# nw2s-b2dsp-panel.net
KiCad netlist of a schematic drawn in EAGLE
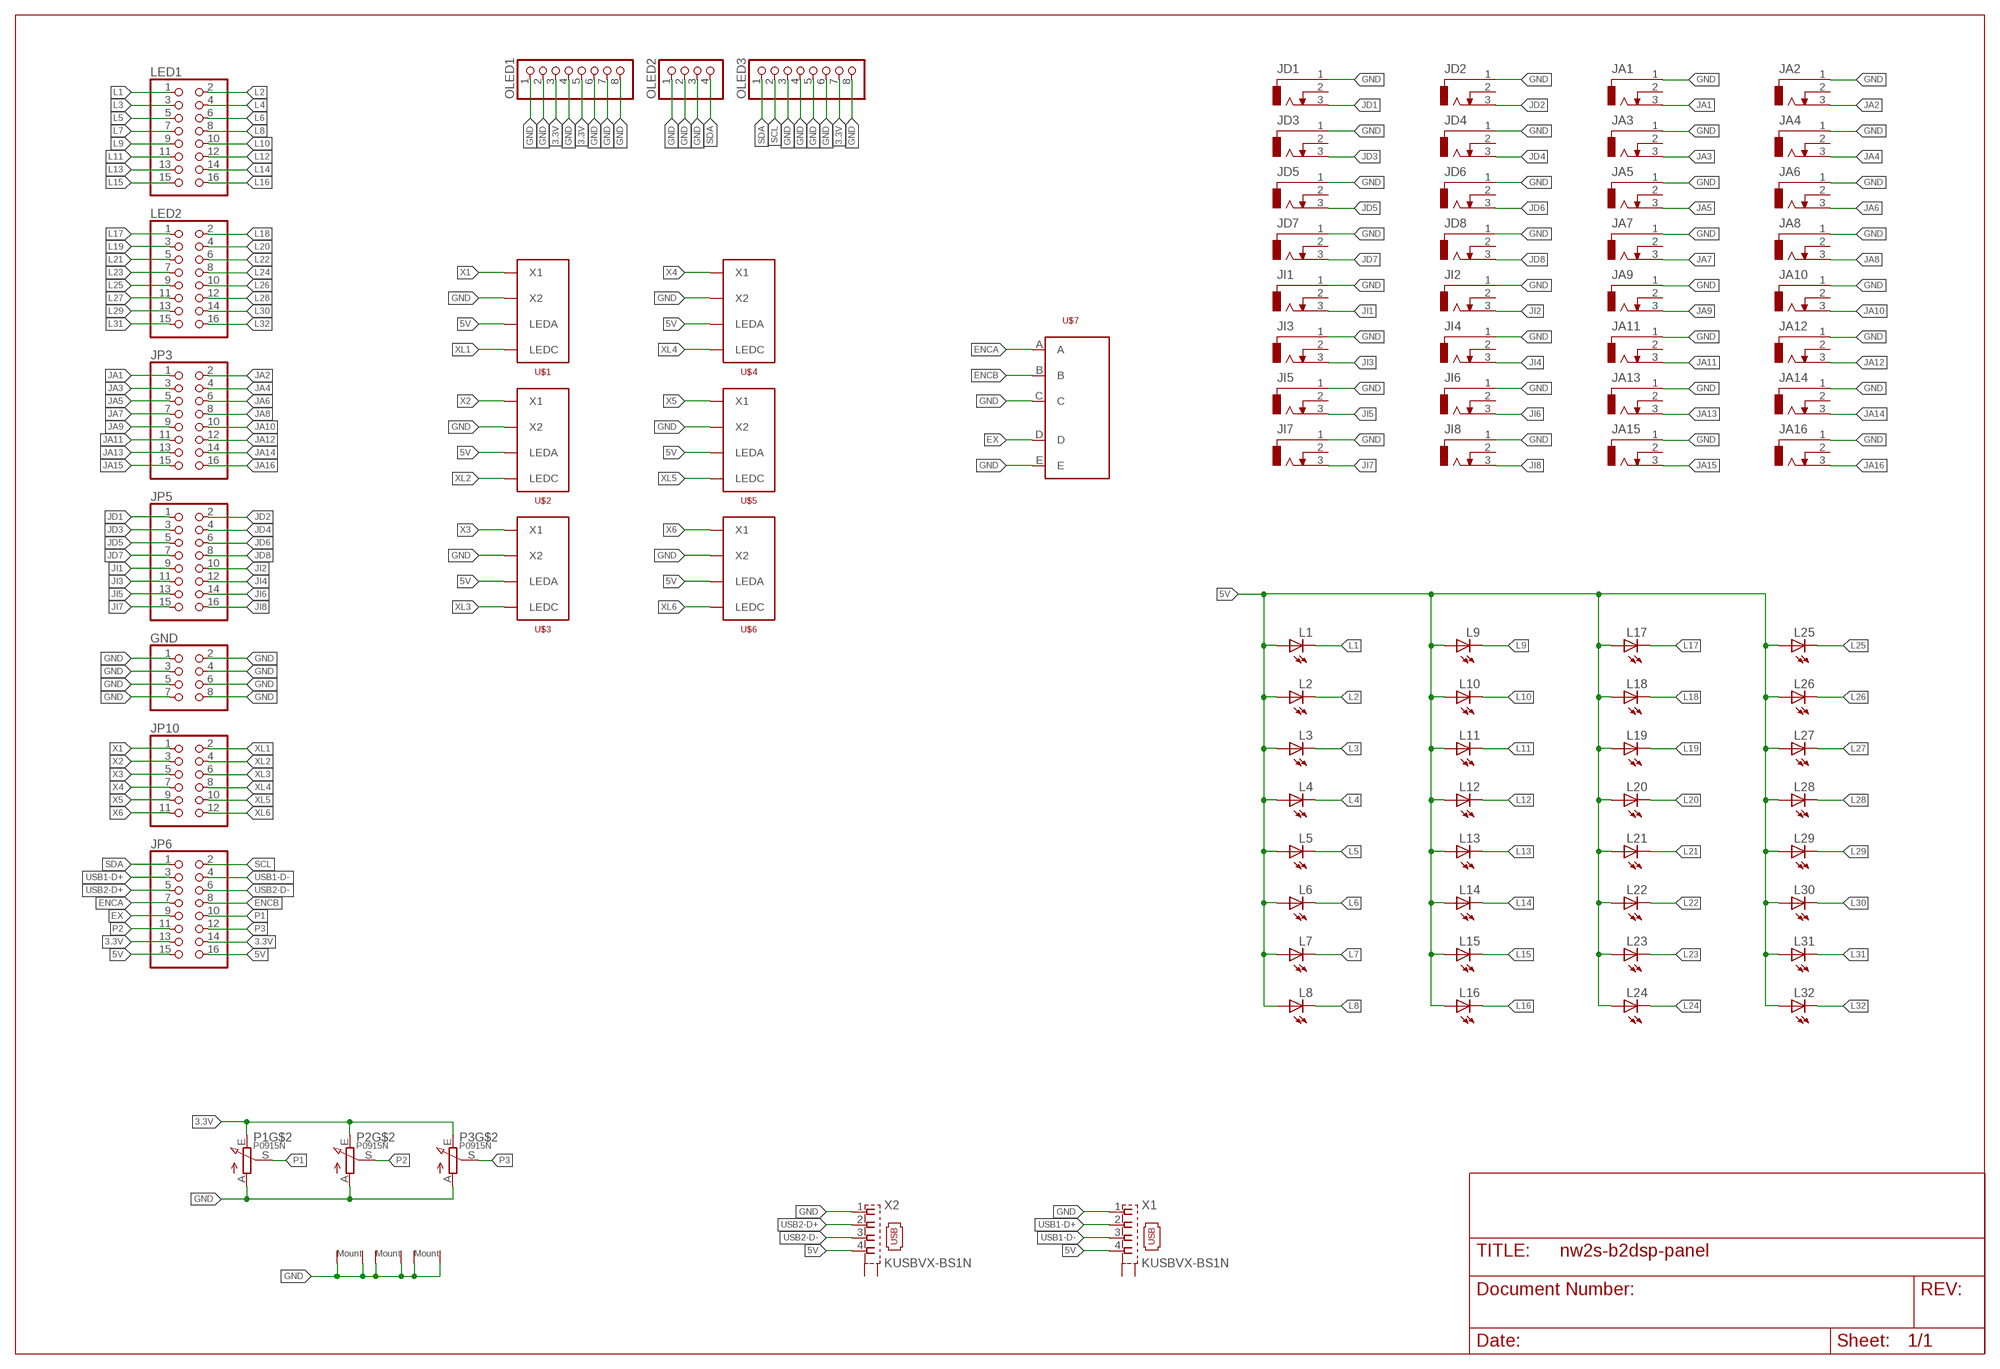
[diagram p0: schematic, sheet 1]

(export (version "E")
  (design (tool "Eeschema 10.0.6"))
  (components
    (comp (ref "GND")
      (value "PINHD-2X4")
      (footprint "eagle-import:2X04")
      (libsource (lib "eagle-import") (part "PINHD-2X4"))
    )
    (comp (ref "JA1")
      (value "THONK35A2")
      (footprint "eagle-import:THONK35A-2")
      (libsource (lib "eagle-import") (part "THONK35A2"))
    )
    (comp (ref "JA2")
      (value "THONK35A2")
      (footprint "eagle-import:THONK35A-2")
      (libsource (lib "eagle-import") (part "THONK35A2"))
    )
    (comp (ref "JA3")
      (value "THONK35A2")
      (footprint "eagle-import:THONK35A-2")
      (libsource (lib "eagle-import") (part "THONK35A2"))
    )
    (comp (ref "JA4")
      (value "THONK35A2")
      (footprint "eagle-import:THONK35A-2")
      (libsource (lib "eagle-import") (part "THONK35A2"))
    )
    (comp (ref "JA5")
      (value "THONK35A2")
      (footprint "eagle-import:THONK35A-2")
      (libsource (lib "eagle-import") (part "THONK35A2"))
    )
    (comp (ref "JA6")
      (value "THONK35A2")
      (footprint "eagle-import:THONK35A-2")
      (libsource (lib "eagle-import") (part "THONK35A2"))
    )
    (comp (ref "JA7")
      (value "THONK35A2")
      (footprint "eagle-import:THONK35A-2")
      (libsource (lib "eagle-import") (part "THONK35A2"))
    )
    (comp (ref "JA8")
      (value "THONK35A2")
      (footprint "eagle-import:THONK35A-2")
      (libsource (lib "eagle-import") (part "THONK35A2"))
    )
    (comp (ref "JA9")
      (value "THONK35A2")
      (footprint "eagle-import:THONK35A-2")
      (libsource (lib "eagle-import") (part "THONK35A2"))
    )
    (comp (ref "JA10")
      (value "THONK35A2")
      (footprint "eagle-import:THONK35A-2")
      (libsource (lib "eagle-import") (part "THONK35A2"))
    )
    (comp (ref "JA11")
      (value "THONK35A2")
      (footprint "eagle-import:THONK35A-2")
      (libsource (lib "eagle-import") (part "THONK35A2"))
    )
    (comp (ref "JA12")
      (value "THONK35A2")
      (footprint "eagle-import:THONK35A-2")
      (libsource (lib "eagle-import") (part "THONK35A2"))
    )
    (comp (ref "JA13")
      (value "THONK35A2")
      (footprint "eagle-import:THONK35A-2")
      (libsource (lib "eagle-import") (part "THONK35A2"))
    )
    (comp (ref "JA14")
      (value "THONK35A2")
      (footprint "eagle-import:THONK35A-2")
      (libsource (lib "eagle-import") (part "THONK35A2"))
    )
    (comp (ref "JA15")
      (value "THONK35A2")
      (footprint "eagle-import:THONK35A-2")
      (libsource (lib "eagle-import") (part "THONK35A2"))
    )
    (comp (ref "JA16")
      (value "THONK35A2")
      (footprint "eagle-import:THONK35A-2")
      (libsource (lib "eagle-import") (part "THONK35A2"))
    )
    (comp (ref "JD1")
      (value "THONK35A2")
      (footprint "eagle-import:THONK35A-2")
      (libsource (lib "eagle-import") (part "THONK35A2"))
    )
    (comp (ref "JD2")
      (value "THONK35A2")
      (footprint "eagle-import:THONK35A-2")
      (libsource (lib "eagle-import") (part "THONK35A2"))
    )
    (comp (ref "JD3")
      (value "THONK35A2")
      (footprint "eagle-import:THONK35A-2")
      (libsource (lib "eagle-import") (part "THONK35A2"))
    )
    (comp (ref "JD4")
      (value "THONK35A2")
      (footprint "eagle-import:THONK35A-2")
      (libsource (lib "eagle-import") (part "THONK35A2"))
    )
    (comp (ref "JD5")
      (value "THONK35A2")
      (footprint "eagle-import:THONK35A-2")
      (libsource (lib "eagle-import") (part "THONK35A2"))
    )
    (comp (ref "JD6")
      (value "THONK35A2")
      (footprint "eagle-import:THONK35A-2")
      (libsource (lib "eagle-import") (part "THONK35A2"))
    )
    (comp (ref "JD7")
      (value "THONK35A2")
      (footprint "eagle-import:THONK35A-2")
      (libsource (lib "eagle-import") (part "THONK35A2"))
    )
    (comp (ref "JD8")
      (value "THONK35A2")
      (footprint "eagle-import:THONK35A-2")
      (libsource (lib "eagle-import") (part "THONK35A2"))
    )
    (comp (ref "JI1")
      (value "THONK35A2")
      (footprint "eagle-import:THONK35A-2")
      (libsource (lib "eagle-import") (part "THONK35A2"))
    )
    (comp (ref "JI2")
      (value "THONK35A2")
      (footprint "eagle-import:THONK35A-2")
      (libsource (lib "eagle-import") (part "THONK35A2"))
    )
    (comp (ref "JI3")
      (value "THONK35A2")
      (footprint "eagle-import:THONK35A-2")
      (libsource (lib "eagle-import") (part "THONK35A2"))
    )
    (comp (ref "JI4")
      (value "THONK35A2")
      (footprint "eagle-import:THONK35A-2")
      (libsource (lib "eagle-import") (part "THONK35A2"))
    )
    (comp (ref "JI5")
      (value "THONK35A2")
      (footprint "eagle-import:THONK35A-2")
      (libsource (lib "eagle-import") (part "THONK35A2"))
    )
    (comp (ref "JI6")
      (value "THONK35A2")
      (footprint "eagle-import:THONK35A-2")
      (libsource (lib "eagle-import") (part "THONK35A2"))
    )
    (comp (ref "JI7")
      (value "THONK35A2")
      (footprint "eagle-import:THONK35A-2")
      (libsource (lib "eagle-import") (part "THONK35A2"))
    )
    (comp (ref "JI8")
      (value "THONK35A2")
      (footprint "eagle-import:THONK35A-2")
      (libsource (lib "eagle-import") (part "THONK35A2"))
    )
    (comp (ref "JP3")
      (value "PINHD-2X8")
      (footprint "eagle-import:2X08")
      (libsource (lib "eagle-import") (part "PINHD-2X8"))
    )
    (comp (ref "JP5")
      (value "PINHD-2X8")
      (footprint "eagle-import:2X08")
      (libsource (lib "eagle-import") (part "PINHD-2X8"))
    )
    (comp (ref "JP6")
      (value "PINHD-2X8")
      (footprint "eagle-import:2X08")
      (libsource (lib "eagle-import") (part "PINHD-2X8"))
    )
    (comp (ref "JP10")
      (value "PINHD-2X6")
      (footprint "eagle-import:2X06")
      (libsource (lib "eagle-import") (part "PINHD-2X6"))
    )
    (comp (ref "L1")
      (value "LED3MM")
      (footprint "eagle-import:LED3MM")
      (libsource (lib "eagle-import") (part "LED3MM"))
    )
    (comp (ref "L2")
      (value "LED3MM")
      (footprint "eagle-import:LED3MM")
      (libsource (lib "eagle-import") (part "LED3MM"))
    )
    (comp (ref "L3")
      (value "LED3MM")
      (footprint "eagle-import:LED3MM")
      (libsource (lib "eagle-import") (part "LED3MM"))
    )
    (comp (ref "L4")
      (value "LED3MM")
      (footprint "eagle-import:LED3MM")
      (libsource (lib "eagle-import") (part "LED3MM"))
    )
    (comp (ref "L5")
      (value "LED3MM")
      (footprint "eagle-import:LED3MM")
      (libsource (lib "eagle-import") (part "LED3MM"))
    )
    (comp (ref "L6")
      (value "LED3MM")
      (footprint "eagle-import:LED3MM")
      (libsource (lib "eagle-import") (part "LED3MM"))
    )
    (comp (ref "L7")
      (value "LED3MM")
      (footprint "eagle-import:LED3MM")
      (libsource (lib "eagle-import") (part "LED3MM"))
    )
    (comp (ref "L8")
      (value "LED3MM")
      (footprint "eagle-import:LED3MM")
      (libsource (lib "eagle-import") (part "LED3MM"))
    )
    (comp (ref "L9")
      (value "LED3MM")
      (footprint "eagle-import:LED3MM")
      (libsource (lib "eagle-import") (part "LED3MM"))
    )
    (comp (ref "L10")
      (value "LED3MM")
      (footprint "eagle-import:LED3MM")
      (libsource (lib "eagle-import") (part "LED3MM"))
    )
    (comp (ref "L11")
      (value "LED3MM")
      (footprint "eagle-import:LED3MM")
      (libsource (lib "eagle-import") (part "LED3MM"))
    )
    (comp (ref "L12")
      (value "LED3MM")
      (footprint "eagle-import:LED3MM")
      (libsource (lib "eagle-import") (part "LED3MM"))
    )
    (comp (ref "L13")
      (value "LED3MM")
      (footprint "eagle-import:LED3MM")
      (libsource (lib "eagle-import") (part "LED3MM"))
    )
    (comp (ref "L14")
      (value "LED3MM")
      (footprint "eagle-import:LED3MM")
      (libsource (lib "eagle-import") (part "LED3MM"))
    )
    (comp (ref "L15")
      (value "LED3MM")
      (footprint "eagle-import:LED3MM")
      (libsource (lib "eagle-import") (part "LED3MM"))
    )
    (comp (ref "L16")
      (value "LED3MM")
      (footprint "eagle-import:LED3MM")
      (libsource (lib "eagle-import") (part "LED3MM"))
    )
    (comp (ref "L17")
      (value "LED3MM")
      (footprint "eagle-import:LED3MM")
      (libsource (lib "eagle-import") (part "LED3MM"))
    )
    (comp (ref "L18")
      (value "LED3MM")
      (footprint "eagle-import:LED3MM")
      (libsource (lib "eagle-import") (part "LED3MM"))
    )
    (comp (ref "L19")
      (value "LED3MM")
      (footprint "eagle-import:LED3MM")
      (libsource (lib "eagle-import") (part "LED3MM"))
    )
    (comp (ref "L20")
      (value "LED3MM")
      (footprint "eagle-import:LED3MM")
      (libsource (lib "eagle-import") (part "LED3MM"))
    )
    (comp (ref "L21")
      (value "LED3MM")
      (footprint "eagle-import:LED3MM")
      (libsource (lib "eagle-import") (part "LED3MM"))
    )
    (comp (ref "L22")
      (value "LED3MM")
      (footprint "eagle-import:LED3MM")
      (libsource (lib "eagle-import") (part "LED3MM"))
    )
    (comp (ref "L23")
      (value "LED3MM")
      (footprint "eagle-import:LED3MM")
      (libsource (lib "eagle-import") (part "LED3MM"))
    )
    (comp (ref "L24")
      (value "LED3MM")
      (footprint "eagle-import:LED3MM")
      (libsource (lib "eagle-import") (part "LED3MM"))
    )
    (comp (ref "L25")
      (value "LED3MM")
      (footprint "eagle-import:LED3MM")
      (libsource (lib "eagle-import") (part "LED3MM"))
    )
    (comp (ref "L26")
      (value "LED3MM")
      (footprint "eagle-import:LED3MM")
      (libsource (lib "eagle-import") (part "LED3MM"))
    )
    (comp (ref "L27")
      (value "LED3MM")
      (footprint "eagle-import:LED3MM")
      (libsource (lib "eagle-import") (part "LED3MM"))
    )
    (comp (ref "L28")
      (value "LED3MM")
      (footprint "eagle-import:LED3MM")
      (libsource (lib "eagle-import") (part "LED3MM"))
    )
    (comp (ref "L29")
      (value "LED3MM")
      (footprint "eagle-import:LED3MM")
      (libsource (lib "eagle-import") (part "LED3MM"))
    )
    (comp (ref "L30")
      (value "LED3MM")
      (footprint "eagle-import:LED3MM")
      (libsource (lib "eagle-import") (part "LED3MM"))
    )
    (comp (ref "L31")
      (value "LED3MM")
      (footprint "eagle-import:LED3MM")
      (libsource (lib "eagle-import") (part "LED3MM"))
    )
    (comp (ref "L32")
      (value "LED3MM")
      (footprint "eagle-import:LED3MM")
      (libsource (lib "eagle-import") (part "LED3MM"))
    )
    (comp (ref "LED1")
      (value "PINHD-2X8")
      (footprint "eagle-import:2X08")
      (libsource (lib "eagle-import") (part "PINHD-2X8"))
    )
    (comp (ref "LED2")
      (value "PINHD-2X8")
      (footprint "eagle-import:2X08")
      (libsource (lib "eagle-import") (part "PINHD-2X8"))
    )
    (comp (ref "OLED1")
      (value "PINHD-1X8")
      (footprint "eagle-import:1X08")
      (libsource (lib "eagle-import") (part "PINHD-1X8"))
    )
    (comp (ref "OLED2")
      (value "PINHD-1X4")
      (footprint "eagle-import:1X04")
      (libsource (lib "eagle-import") (part "PINHD-1X4"))
    )
    (comp (ref "OLED3")
      (value "PINHD-1X8")
      (footprint "eagle-import:1X08")
      (libsource (lib "eagle-import") (part "PINHD-1X8"))
    )
    (comp (ref "P1")
      (value "P0915N")
      (footprint "eagle-import:P0915N")
      (libsource (lib "eagle-import") (part "P0915N"))
    )
    (comp (ref "P2")
      (value "P0915N")
      (footprint "eagle-import:P0915N")
      (libsource (lib "eagle-import") (part "P0915N"))
    )
    (comp (ref "P3")
      (value "P0915N")
      (footprint "eagle-import:P0915N")
      (libsource (lib "eagle-import") (part "P0915N"))
    )
    (comp (ref "U$1")
      (value "MEC5G")
      (footprint "eagle-import:MEC5G")
      (libsource (lib "eagle-import") (part "MEC5G"))
    )
    (comp (ref "U$2")
      (value "MEC5G")
      (footprint "eagle-import:MEC5G")
      (libsource (lib "eagle-import") (part "MEC5G"))
    )
    (comp (ref "U$3")
      (value "MEC5G")
      (footprint "eagle-import:MEC5G")
      (libsource (lib "eagle-import") (part "MEC5G"))
    )
    (comp (ref "U$4")
      (value "MEC5G")
      (footprint "eagle-import:MEC5G")
      (libsource (lib "eagle-import") (part "MEC5G"))
    )
    (comp (ref "U$5")
      (value "MEC5G")
      (footprint "eagle-import:MEC5G")
      (libsource (lib "eagle-import") (part "MEC5G"))
    )
    (comp (ref "U$6")
      (value "MEC5G")
      (footprint "eagle-import:MEC5G")
      (libsource (lib "eagle-import") (part "MEC5G"))
    )
    (comp (ref "U$7")
      (value "EN11X")
      (footprint "eagle-import:EN11")
      (libsource (lib "eagle-import") (part "EN11X"))
    )
    (comp (ref "X1")
      (value "KUSBVX-BS1N")
      (footprint "eagle-import:KUSBVX-BS1N")
      (libsource (lib "eagle-import") (part "KUSBVX-BS1N"))
    )
    (comp (ref "X2")
      (value "KUSBVX-BS1N")
      (footprint "eagle-import:KUSBVX-BS1N")
      (libsource (lib "eagle-import") (part "KUSBVX-BS1N"))
    )
  )
  (nets
    (net (code "1") (name "3.3V") (class "Default")
      (node (ref "JP6") (pin "13") (pinfunction "13_13") (pintype "passive"))
      (node (ref "JP6") (pin "14") (pinfunction "14_14") (pintype "passive"))
      (node (ref "OLED1") (pin "3") (pinfunction "3_3") (pintype "passive"))
      (node (ref "OLED1") (pin "5") (pinfunction "5_5") (pintype "passive"))
      (node (ref "OLED3") (pin "7") (pinfunction "7_7") (pintype "passive"))
      (node (ref "P1") (pin "E") (pinfunction "E_E") (pintype "passive"))
      (node (ref "P2") (pin "E") (pinfunction "E_E") (pintype "passive"))
      (node (ref "P3") (pin "E") (pinfunction "E_E") (pintype "passive"))
    )
    (net (code "2") (name "5V") (class "Default")
      (node (ref "JP6") (pin "15") (pinfunction "15_15") (pintype "passive"))
      (node (ref "JP6") (pin "16") (pinfunction "16_16") (pintype "passive"))
      (node (ref "L1") (pin "A") (pinfunction "A_A") (pintype "passive"))
      (node (ref "L10") (pin "A") (pinfunction "A_A") (pintype "passive"))
      (node (ref "L11") (pin "A") (pinfunction "A_A") (pintype "passive"))
      (node (ref "L12") (pin "A") (pinfunction "A_A") (pintype "passive"))
      (node (ref "L13") (pin "A") (pinfunction "A_A") (pintype "passive"))
      (node (ref "L14") (pin "A") (pinfunction "A_A") (pintype "passive"))
      (node (ref "L15") (pin "A") (pinfunction "A_A") (pintype "passive"))
      (node (ref "L16") (pin "A") (pinfunction "A_A") (pintype "passive"))
      (node (ref "L17") (pin "A") (pinfunction "A_A") (pintype "passive"))
      (node (ref "L18") (pin "A") (pinfunction "A_A") (pintype "passive"))
      (node (ref "L19") (pin "A") (pinfunction "A_A") (pintype "passive"))
      (node (ref "L2") (pin "A") (pinfunction "A_A") (pintype "passive"))
      (node (ref "L20") (pin "A") (pinfunction "A_A") (pintype "passive"))
      (node (ref "L21") (pin "A") (pinfunction "A_A") (pintype "passive"))
      (node (ref "L22") (pin "A") (pinfunction "A_A") (pintype "passive"))
      (node (ref "L23") (pin "A") (pinfunction "A_A") (pintype "passive"))
      (node (ref "L24") (pin "A") (pinfunction "A_A") (pintype "passive"))
      (node (ref "L25") (pin "A") (pinfunction "A_A") (pintype "passive"))
      (node (ref "L26") (pin "A") (pinfunction "A_A") (pintype "passive"))
      (node (ref "L27") (pin "A") (pinfunction "A_A") (pintype "passive"))
      (node (ref "L28") (pin "A") (pinfunction "A_A") (pintype "passive"))
      (node (ref "L29") (pin "A") (pinfunction "A_A") (pintype "passive"))
      (node (ref "L3") (pin "A") (pinfunction "A_A") (pintype "passive"))
      (node (ref "L30") (pin "A") (pinfunction "A_A") (pintype "passive"))
      (node (ref "L31") (pin "A") (pinfunction "A_A") (pintype "passive"))
      (node (ref "L32") (pin "A") (pinfunction "A_A") (pintype "passive"))
      (node (ref "L4") (pin "A") (pinfunction "A_A") (pintype "passive"))
      (node (ref "L5") (pin "A") (pinfunction "A_A") (pintype "passive"))
      (node (ref "L6") (pin "A") (pinfunction "A_A") (pintype "passive"))
      (node (ref "L7") (pin "A") (pinfunction "A_A") (pintype "passive"))
      (node (ref "L8") (pin "A") (pinfunction "A_A") (pintype "passive"))
      (node (ref "L9") (pin "A") (pinfunction "A_A") (pintype "passive"))
      (node (ref "U$1") (pin "P$4") (pinfunction "LEDA_P$4") (pintype "bidirectional"))
      (node (ref "U$2") (pin "P$4") (pinfunction "LEDA_P$4") (pintype "bidirectional"))
      (node (ref "U$3") (pin "P$4") (pinfunction "LEDA_P$4") (pintype "bidirectional"))
      (node (ref "U$4") (pin "P$4") (pinfunction "LEDA_P$4") (pintype "bidirectional"))
      (node (ref "U$5") (pin "P$4") (pinfunction "LEDA_P$4") (pintype "bidirectional"))
      (node (ref "U$6") (pin "P$4") (pinfunction "LEDA_P$4") (pintype "bidirectional"))
      (node (ref "X1") (pin "4") (pinfunction "4_4") (pintype "passive"))
      (node (ref "X2") (pin "4") (pinfunction "4_4") (pintype "passive"))
    )
    (net (code "3") (name "ENCA") (class "Default")
      (node (ref "JP6") (pin "7") (pinfunction "7_7") (pintype "passive"))
      (node (ref "U$7") (pin "A") (pinfunction "A_A") (pintype "bidirectional"))
    )
    (net (code "4") (name "ENCB") (class "Default")
      (node (ref "JP6") (pin "8") (pinfunction "8_8") (pintype "passive"))
      (node (ref "U$7") (pin "B") (pinfunction "B_B") (pintype "bidirectional"))
    )
    (net (code "5") (name "EX") (class "Default")
      (node (ref "JP6") (pin "9") (pinfunction "9_9") (pintype "passive"))
      (node (ref "U$7") (pin "D") (pinfunction "D_D") (pintype "bidirectional"))
    )
    (net (code "6") (name "GND") (class "Default")
      (node (ref "GND") (pin "1") (pinfunction "1_1") (pintype "passive"))
      (node (ref "GND") (pin "2") (pinfunction "2_2") (pintype "passive"))
      (node (ref "GND") (pin "3") (pinfunction "3_3") (pintype "passive"))
      (node (ref "GND") (pin "4") (pinfunction "4_4") (pintype "passive"))
      (node (ref "GND") (pin "5") (pinfunction "5_5") (pintype "passive"))
      (node (ref "GND") (pin "6") (pinfunction "6_6") (pintype "passive"))
      (node (ref "GND") (pin "7") (pinfunction "7_7") (pintype "passive"))
      (node (ref "GND") (pin "8") (pinfunction "8_8") (pintype "passive"))
      (node (ref "JA1") (pin "1") (pinfunction "1_1") (pintype "passive"))
      (node (ref "JA10") (pin "1") (pinfunction "1_1") (pintype "passive"))
      (node (ref "JA11") (pin "1") (pinfunction "1_1") (pintype "passive"))
      (node (ref "JA12") (pin "1") (pinfunction "1_1") (pintype "passive"))
      (node (ref "JA13") (pin "1") (pinfunction "1_1") (pintype "passive"))
      (node (ref "JA14") (pin "1") (pinfunction "1_1") (pintype "passive"))
      (node (ref "JA15") (pin "1") (pinfunction "1_1") (pintype "passive"))
      (node (ref "JA16") (pin "1") (pinfunction "1_1") (pintype "passive"))
      (node (ref "JA2") (pin "1") (pinfunction "1_1") (pintype "passive"))
      (node (ref "JA3") (pin "1") (pinfunction "1_1") (pintype "passive"))
      (node (ref "JA4") (pin "1") (pinfunction "1_1") (pintype "passive"))
      (node (ref "JA5") (pin "1") (pinfunction "1_1") (pintype "passive"))
      (node (ref "JA6") (pin "1") (pinfunction "1_1") (pintype "passive"))
      (node (ref "JA7") (pin "1") (pinfunction "1_1") (pintype "passive"))
      (node (ref "JA8") (pin "1") (pinfunction "1_1") (pintype "passive"))
      (node (ref "JA9") (pin "1") (pinfunction "1_1") (pintype "passive"))
      (node (ref "JD1") (pin "1") (pinfunction "1_1") (pintype "passive"))
      (node (ref "JD2") (pin "1") (pinfunction "1_1") (pintype "passive"))
      (node (ref "JD3") (pin "1") (pinfunction "1_1") (pintype "passive"))
      (node (ref "JD4") (pin "1") (pinfunction "1_1") (pintype "passive"))
      (node (ref "JD5") (pin "1") (pinfunction "1_1") (pintype "passive"))
      (node (ref "JD6") (pin "1") (pinfunction "1_1") (pintype "passive"))
      (node (ref "JD7") (pin "1") (pinfunction "1_1") (pintype "passive"))
      (node (ref "JD8") (pin "1") (pinfunction "1_1") (pintype "passive"))
      (node (ref "JI1") (pin "1") (pinfunction "1_1") (pintype "passive"))
      (node (ref "JI2") (pin "1") (pinfunction "1_1") (pintype "passive"))
      (node (ref "JI3") (pin "1") (pinfunction "1_1") (pintype "passive"))
      (node (ref "JI4") (pin "1") (pinfunction "1_1") (pintype "passive"))
      (node (ref "JI5") (pin "1") (pinfunction "1_1") (pintype "passive"))
      (node (ref "JI6") (pin "1") (pinfunction "1_1") (pintype "passive"))
      (node (ref "JI7") (pin "1") (pinfunction "1_1") (pintype "passive"))
      (node (ref "JI8") (pin "1") (pinfunction "1_1") (pintype "passive"))
      (node (ref "OLED1") (pin "1") (pinfunction "1_1") (pintype "passive"))
      (node (ref "OLED1") (pin "2") (pinfunction "2_2") (pintype "passive"))
      (node (ref "OLED1") (pin "4") (pinfunction "4_4") (pintype "passive"))
      (node (ref "OLED1") (pin "6") (pinfunction "6_6") (pintype "passive"))
      (node (ref "OLED1") (pin "7") (pinfunction "7_7") (pintype "passive"))
      (node (ref "OLED1") (pin "8") (pinfunction "8_8") (pintype "passive"))
      (node (ref "OLED2") (pin "1") (pinfunction "1_1") (pintype "passive"))
      (node (ref "OLED2") (pin "2") (pinfunction "2_2") (pintype "passive"))
      (node (ref "OLED2") (pin "3") (pinfunction "3_3") (pintype "passive"))
      (node (ref "OLED3") (pin "3") (pinfunction "3_3") (pintype "passive"))
      (node (ref "OLED3") (pin "4") (pinfunction "4_4") (pintype "passive"))
      (node (ref "OLED3") (pin "5") (pinfunction "5_5") (pintype "passive"))
      (node (ref "OLED3") (pin "6") (pinfunction "6_6") (pintype "passive"))
      (node (ref "OLED3") (pin "8") (pinfunction "8_8") (pintype "passive"))
      (node (ref "P1") (pin "A") (pinfunction "A_A") (pintype "passive"))
      (node (ref "P1") (pin "GND@1") (pinfunction "GND_GND@1") (pintype "passive"))
      (node (ref "P1") (pin "GND@2") (pinfunction "GND_GND@2") (pintype "passive"))
      (node (ref "P2") (pin "A") (pinfunction "A_A") (pintype "passive"))
      (node (ref "P2") (pin "GND@1") (pinfunction "GND_GND@1") (pintype "passive"))
      (node (ref "P2") (pin "GND@2") (pinfunction "GND_GND@2") (pintype "passive"))
      (node (ref "P3") (pin "A") (pinfunction "A_A") (pintype "passive"))
      (node (ref "P3") (pin "GND@1") (pinfunction "GND_GND@1") (pintype "passive"))
      (node (ref "P3") (pin "GND@2") (pinfunction "GND_GND@2") (pintype "passive"))
      (node (ref "U$1") (pin "P$3") (pinfunction "X2_P$3") (pintype "bidirectional"))
      (node (ref "U$2") (pin "P$3") (pinfunction "X2_P$3") (pintype "bidirectional"))
      (node (ref "U$3") (pin "P$3") (pinfunction "X2_P$3") (pintype "bidirectional"))
      (node (ref "U$4") (pin "P$3") (pinfunction "X2_P$3") (pintype "bidirectional"))
      (node (ref "U$5") (pin "P$3") (pinfunction "X2_P$3") (pintype "bidirectional"))
      (node (ref "U$6") (pin "P$3") (pinfunction "X2_P$3") (pintype "bidirectional"))
      (node (ref "U$7") (pin "C") (pinfunction "C_C") (pintype "bidirectional"))
      (node (ref "U$7") (pin "E") (pinfunction "E_E") (pintype "bidirectional"))
      (node (ref "X1") (pin "1") (pinfunction "1_1") (pintype "passive"))
      (node (ref "X2") (pin "1") (pinfunction "1_1") (pintype "passive"))
    )
    (net (code "7") (name "JA1") (class "Default")
      (node (ref "JA1") (pin "3") (pinfunction "3_3") (pintype "passive"))
      (node (ref "JP3") (pin "1") (pinfunction "1_1") (pintype "passive"))
    )
    (net (code "8") (name "JA2") (class "Default")
      (node (ref "JA2") (pin "3") (pinfunction "3_3") (pintype "passive"))
      (node (ref "JP3") (pin "2") (pinfunction "2_2") (pintype "passive"))
    )
    (net (code "9") (name "JA3") (class "Default")
      (node (ref "JA3") (pin "3") (pinfunction "3_3") (pintype "passive"))
      (node (ref "JP3") (pin "3") (pinfunction "3_3") (pintype "passive"))
    )
    (net (code "10") (name "JA4") (class "Default")
      (node (ref "JA4") (pin "3") (pinfunction "3_3") (pintype "passive"))
      (node (ref "JP3") (pin "4") (pinfunction "4_4") (pintype "passive"))
    )
    (net (code "11") (name "JA5") (class "Default")
      (node (ref "JA5") (pin "3") (pinfunction "3_3") (pintype "passive"))
      (node (ref "JP3") (pin "5") (pinfunction "5_5") (pintype "passive"))
    )
    (net (code "12") (name "JA6") (class "Default")
      (node (ref "JA6") (pin "3") (pinfunction "3_3") (pintype "passive"))
      (node (ref "JP3") (pin "6") (pinfunction "6_6") (pintype "passive"))
    )
    (net (code "13") (name "JA7") (class "Default")
      (node (ref "JA7") (pin "3") (pinfunction "3_3") (pintype "passive"))
      (node (ref "JP3") (pin "7") (pinfunction "7_7") (pintype "passive"))
    )
    (net (code "14") (name "JA8") (class "Default")
      (node (ref "JA8") (pin "3") (pinfunction "3_3") (pintype "passive"))
      (node (ref "JP3") (pin "8") (pinfunction "8_8") (pintype "passive"))
    )
    (net (code "15") (name "JA9") (class "Default")
      (node (ref "JA9") (pin "3") (pinfunction "3_3") (pintype "passive"))
      (node (ref "JP3") (pin "9") (pinfunction "9_9") (pintype "passive"))
    )
    (net (code "16") (name "JA10") (class "Default")
      (node (ref "JA10") (pin "3") (pinfunction "3_3") (pintype "passive"))
      (node (ref "JP3") (pin "10") (pinfunction "10_10") (pintype "passive"))
    )
    (net (code "17") (name "JA11") (class "Default")
      (node (ref "JA11") (pin "3") (pinfunction "3_3") (pintype "passive"))
      (node (ref "JP3") (pin "11") (pinfunction "11_11") (pintype "passive"))
    )
    (net (code "18") (name "JA12") (class "Default")
      (node (ref "JA12") (pin "3") (pinfunction "3_3") (pintype "passive"))
      (node (ref "JP3") (pin "12") (pinfunction "12_12") (pintype "passive"))
    )
    (net (code "19") (name "JA13") (class "Default")
      (node (ref "JA13") (pin "3") (pinfunction "3_3") (pintype "passive"))
      (node (ref "JP3") (pin "13") (pinfunction "13_13") (pintype "passive"))
    )
    (net (code "20") (name "JA14") (class "Default")
      (node (ref "JA14") (pin "3") (pinfunction "3_3") (pintype "passive"))
      (node (ref "JP3") (pin "14") (pinfunction "14_14") (pintype "passive"))
    )
    (net (code "21") (name "JA15") (class "Default")
      (node (ref "JA15") (pin "3") (pinfunction "3_3") (pintype "passive"))
      (node (ref "JP3") (pin "15") (pinfunction "15_15") (pintype "passive"))
    )
    (net (code "22") (name "JA16") (class "Default")
      (node (ref "JA16") (pin "3") (pinfunction "3_3") (pintype "passive"))
      (node (ref "JP3") (pin "16") (pinfunction "16_16") (pintype "passive"))
    )
    (net (code "23") (name "JD1") (class "Default")
      (node (ref "JD1") (pin "3") (pinfunction "3_3") (pintype "passive"))
      (node (ref "JP5") (pin "1") (pinfunction "1_1") (pintype "passive"))
    )
    (net (code "24") (name "JD2") (class "Default")
      (node (ref "JD2") (pin "3") (pinfunction "3_3") (pintype "passive"))
      (node (ref "JP5") (pin "2") (pinfunction "2_2") (pintype "passive"))
    )
    (net (code "25") (name "JD3") (class "Default")
      (node (ref "JD3") (pin "3") (pinfunction "3_3") (pintype "passive"))
      (node (ref "JP5") (pin "3") (pinfunction "3_3") (pintype "passive"))
    )
    (net (code "26") (name "JD4") (class "Default")
      (node (ref "JD4") (pin "3") (pinfunction "3_3") (pintype "passive"))
      (node (ref "JP5") (pin "4") (pinfunction "4_4") (pintype "passive"))
    )
    (net (code "27") (name "JD5") (class "Default")
      (node (ref "JD5") (pin "3") (pinfunction "3_3") (pintype "passive"))
      (node (ref "JP5") (pin "5") (pinfunction "5_5") (pintype "passive"))
    )
    (net (code "28") (name "JD6") (class "Default")
      (node (ref "JD6") (pin "3") (pinfunction "3_3") (pintype "passive"))
      (node (ref "JP5") (pin "6") (pinfunction "6_6") (pintype "passive"))
    )
    (net (code "29") (name "JD7") (class "Default")
      (node (ref "JD7") (pin "3") (pinfunction "3_3") (pintype "passive"))
      (node (ref "JP5") (pin "7") (pinfunction "7_7") (pintype "passive"))
    )
    (net (code "30") (name "JD8") (class "Default")
      (node (ref "JD8") (pin "3") (pinfunction "3_3") (pintype "passive"))
      (node (ref "JP5") (pin "8") (pinfunction "8_8") (pintype "passive"))
    )
    (net (code "31") (name "JI1") (class "Default")
      (node (ref "JI1") (pin "3") (pinfunction "3_3") (pintype "passive"))
      (node (ref "JP5") (pin "9") (pinfunction "9_9") (pintype "passive"))
    )
    (net (code "32") (name "JI2") (class "Default")
      (node (ref "JI2") (pin "3") (pinfunction "3_3") (pintype "passive"))
      (node (ref "JP5") (pin "10") (pinfunction "10_10") (pintype "passive"))
    )
    (net (code "33") (name "JI3") (class "Default")
      (node (ref "JI3") (pin "3") (pinfunction "3_3") (pintype "passive"))
      (node (ref "JP5") (pin "11") (pinfunction "11_11") (pintype "passive"))
    )
    (net (code "34") (name "JI4") (class "Default")
      (node (ref "JI4") (pin "3") (pinfunction "3_3") (pintype "passive"))
      (node (ref "JP5") (pin "12") (pinfunction "12_12") (pintype "passive"))
    )
    (net (code "35") (name "JI5") (class "Default")
      (node (ref "JI5") (pin "3") (pinfunction "3_3") (pintype "passive"))
      (node (ref "JP5") (pin "13") (pinfunction "13_13") (pintype "passive"))
    )
    (net (code "36") (name "JI6") (class "Default")
      (node (ref "JI6") (pin "3") (pinfunction "3_3") (pintype "passive"))
      (node (ref "JP5") (pin "14") (pinfunction "14_14") (pintype "passive"))
    )
    (net (code "37") (name "JI7") (class "Default")
      (node (ref "JI7") (pin "3") (pinfunction "3_3") (pintype "passive"))
      (node (ref "JP5") (pin "15") (pinfunction "15_15") (pintype "passive"))
    )
    (net (code "38") (name "JI8") (class "Default")
      (node (ref "JI8") (pin "3") (pinfunction "3_3") (pintype "passive"))
      (node (ref "JP5") (pin "16") (pinfunction "16_16") (pintype "passive"))
    )
    (net (code "39") (name "L1") (class "Default")
      (node (ref "L1") (pin "K") (pinfunction "C_K") (pintype "passive"))
      (node (ref "LED1") (pin "1") (pinfunction "1_1") (pintype "passive"))
    )
    (net (code "40") (name "L2") (class "Default")
      (node (ref "L2") (pin "K") (pinfunction "C_K") (pintype "passive"))
      (node (ref "LED1") (pin "2") (pinfunction "2_2") (pintype "passive"))
    )
    (net (code "41") (name "L3") (class "Default")
      (node (ref "L3") (pin "K") (pinfunction "C_K") (pintype "passive"))
      (node (ref "LED1") (pin "3") (pinfunction "3_3") (pintype "passive"))
    )
    (net (code "42") (name "L4") (class "Default")
      (node (ref "L4") (pin "K") (pinfunction "C_K") (pintype "passive"))
      (node (ref "LED1") (pin "4") (pinfunction "4_4") (pintype "passive"))
    )
    (net (code "43") (name "L5") (class "Default")
      (node (ref "L5") (pin "K") (pinfunction "C_K") (pintype "passive"))
      (node (ref "LED1") (pin "5") (pinfunction "5_5") (pintype "passive"))
    )
    (net (code "44") (name "L6") (class "Default")
      (node (ref "L6") (pin "K") (pinfunction "C_K") (pintype "passive"))
      (node (ref "LED1") (pin "6") (pinfunction "6_6") (pintype "passive"))
    )
    (net (code "45") (name "L7") (class "Default")
      (node (ref "L7") (pin "K") (pinfunction "C_K") (pintype "passive"))
      (node (ref "LED1") (pin "7") (pinfunction "7_7") (pintype "passive"))
    )
    (net (code "46") (name "L8") (class "Default")
      (node (ref "L8") (pin "K") (pinfunction "C_K") (pintype "passive"))
      (node (ref "LED1") (pin "8") (pinfunction "8_8") (pintype "passive"))
    )
    (net (code "47") (name "L9") (class "Default")
      (node (ref "L9") (pin "K") (pinfunction "C_K") (pintype "passive"))
      (node (ref "LED1") (pin "9") (pinfunction "9_9") (pintype "passive"))
    )
    (net (code "48") (name "L10") (class "Default")
      (node (ref "L10") (pin "K") (pinfunction "C_K") (pintype "passive"))
      (node (ref "LED1") (pin "10") (pinfunction "10_10") (pintype "passive"))
    )
    (net (code "49") (name "L11") (class "Default")
      (node (ref "L11") (pin "K") (pinfunction "C_K") (pintype "passive"))
      (node (ref "LED1") (pin "11") (pinfunction "11_11") (pintype "passive"))
    )
    (net (code "50") (name "L12") (class "Default")
      (node (ref "L12") (pin "K") (pinfunction "C_K") (pintype "passive"))
      (node (ref "LED1") (pin "12") (pinfunction "12_12") (pintype "passive"))
    )
    (net (code "51") (name "L13") (class "Default")
      (node (ref "L13") (pin "K") (pinfunction "C_K") (pintype "passive"))
      (node (ref "LED1") (pin "13") (pinfunction "13_13") (pintype "passive"))
    )
    (net (code "52") (name "L14") (class "Default")
      (node (ref "L14") (pin "K") (pinfunction "C_K") (pintype "passive"))
      (node (ref "LED1") (pin "14") (pinfunction "14_14") (pintype "passive"))
    )
    (net (code "53") (name "L15") (class "Default")
      (node (ref "L15") (pin "K") (pinfunction "C_K") (pintype "passive"))
      (node (ref "LED1") (pin "15") (pinfunction "15_15") (pintype "passive"))
    )
    (net (code "54") (name "L16") (class "Default")
      (node (ref "L16") (pin "K") (pinfunction "C_K") (pintype "passive"))
      (node (ref "LED1") (pin "16") (pinfunction "16_16") (pintype "passive"))
    )
    (net (code "55") (name "L17") (class "Default")
      (node (ref "L17") (pin "K") (pinfunction "C_K") (pintype "passive"))
      (node (ref "LED2") (pin "1") (pinfunction "1_1") (pintype "passive"))
    )
    (net (code "56") (name "L18") (class "Default")
      (node (ref "L18") (pin "K") (pinfunction "C_K") (pintype "passive"))
      (node (ref "LED2") (pin "2") (pinfunction "2_2") (pintype "passive"))
    )
    (net (code "57") (name "L19") (class "Default")
      (node (ref "L19") (pin "K") (pinfunction "C_K") (pintype "passive"))
      (node (ref "LED2") (pin "3") (pinfunction "3_3") (pintype "passive"))
    )
    (net (code "58") (name "L20") (class "Default")
      (node (ref "L20") (pin "K") (pinfunction "C_K") (pintype "passive"))
      (node (ref "LED2") (pin "4") (pinfunction "4_4") (pintype "passive"))
    )
    (net (code "59") (name "L21") (class "Default")
      (node (ref "L21") (pin "K") (pinfunction "C_K") (pintype "passive"))
      (node (ref "LED2") (pin "5") (pinfunction "5_5") (pintype "passive"))
    )
    (net (code "60") (name "L22") (class "Default")
      (node (ref "L22") (pin "K") (pinfunction "C_K") (pintype "passive"))
      (node (ref "LED2") (pin "6") (pinfunction "6_6") (pintype "passive"))
    )
    (net (code "61") (name "L23") (class "Default")
      (node (ref "L23") (pin "K") (pinfunction "C_K") (pintype "passive"))
      (node (ref "LED2") (pin "7") (pinfunction "7_7") (pintype "passive"))
    )
    (net (code "62") (name "L24") (class "Default")
      (node (ref "L24") (pin "K") (pinfunction "C_K") (pintype "passive"))
      (node (ref "LED2") (pin "8") (pinfunction "8_8") (pintype "passive"))
    )
    (net (code "63") (name "L25") (class "Default")
      (node (ref "L25") (pin "K") (pinfunction "C_K") (pintype "passive"))
      (node (ref "LED2") (pin "9") (pinfunction "9_9") (pintype "passive"))
    )
    (net (code "64") (name "L26") (class "Default")
      (node (ref "L26") (pin "K") (pinfunction "C_K") (pintype "passive"))
      (node (ref "LED2") (pin "10") (pinfunction "10_10") (pintype "passive"))
    )
    (net (code "65") (name "L27") (class "Default")
      (node (ref "L27") (pin "K") (pinfunction "C_K") (pintype "passive"))
      (node (ref "LED2") (pin "11") (pinfunction "11_11") (pintype "passive"))
    )
    (net (code "66") (name "L28") (class "Default")
      (node (ref "L28") (pin "K") (pinfunction "C_K") (pintype "passive"))
      (node (ref "LED2") (pin "12") (pinfunction "12_12") (pintype "passive"))
    )
    (net (code "67") (name "L29") (class "Default")
      (node (ref "L29") (pin "K") (pinfunction "C_K") (pintype "passive"))
      (node (ref "LED2") (pin "13") (pinfunction "13_13") (pintype "passive"))
    )
    (net (code "68") (name "L30") (class "Default")
      (node (ref "L30") (pin "K") (pinfunction "C_K") (pintype "passive"))
      (node (ref "LED2") (pin "14") (pinfunction "14_14") (pintype "passive"))
    )
    (net (code "69") (name "L31") (class "Default")
      (node (ref "L31") (pin "K") (pinfunction "C_K") (pintype "passive"))
      (node (ref "LED2") (pin "15") (pinfunction "15_15") (pintype "passive"))
    )
    (net (code "70") (name "L32") (class "Default")
      (node (ref "L32") (pin "K") (pinfunction "C_K") (pintype "passive"))
      (node (ref "LED2") (pin "16") (pinfunction "16_16") (pintype "passive"))
    )
    (net (code "71") (name "P1") (class "Default")
      (node (ref "JP6") (pin "10") (pinfunction "10_10") (pintype "passive"))
      (node (ref "P1") (pin "S") (pinfunction "S_S") (pintype "passive"))
    )
    (net (code "72") (name "P2") (class "Default")
      (node (ref "JP6") (pin "11") (pinfunction "11_11") (pintype "passive"))
      (node (ref "P2") (pin "S") (pinfunction "S_S") (pintype "passive"))
    )
    (net (code "73") (name "P3") (class "Default")
      (node (ref "JP6") (pin "12") (pinfunction "12_12") (pintype "passive"))
      (node (ref "P3") (pin "S") (pinfunction "S_S") (pintype "passive"))
    )
    (net (code "74") (name "SCL") (class "Default")
      (node (ref "JP6") (pin "2") (pinfunction "2_2") (pintype "passive"))
      (node (ref "OLED3") (pin "2") (pinfunction "2_2") (pintype "passive"))
    )
    (net (code "75") (name "SDA") (class "Default")
      (node (ref "JP6") (pin "1") (pinfunction "1_1") (pintype "passive"))
      (node (ref "OLED2") (pin "4") (pinfunction "4_4") (pintype "passive"))
      (node (ref "OLED3") (pin "1") (pinfunction "1_1") (pintype "passive"))
    )
    (net (code "76") (name "USB1-D+") (class "Default")
      (node (ref "JP6") (pin "3") (pinfunction "3_3") (pintype "passive"))
      (node (ref "X1") (pin "2") (pinfunction "2_2") (pintype "passive"))
    )
    (net (code "77") (name "USB1-D-") (class "Default")
      (node (ref "JP6") (pin "4") (pinfunction "4_4") (pintype "passive"))
      (node (ref "X1") (pin "3") (pinfunction "3_3") (pintype "passive"))
    )
    (net (code "78") (name "USB2-D+") (class "Default")
      (node (ref "JP6") (pin "5") (pinfunction "5_5") (pintype "passive"))
      (node (ref "X2") (pin "2") (pinfunction "2_2") (pintype "passive"))
    )
    (net (code "79") (name "USB2-D-") (class "Default")
      (node (ref "JP6") (pin "6") (pinfunction "6_6") (pintype "passive"))
      (node (ref "X2") (pin "3") (pinfunction "3_3") (pintype "passive"))
    )
    (net (code "80") (name "X1") (class "Default")
      (node (ref "JP10") (pin "1") (pinfunction "1_1") (pintype "passive"))
      (node (ref "U$1") (pin "P$2") (pinfunction "X1_P$2") (pintype "bidirectional"))
    )
    (net (code "81") (name "X2") (class "Default")
      (node (ref "JP10") (pin "3") (pinfunction "3_3") (pintype "passive"))
      (node (ref "U$2") (pin "P$2") (pinfunction "X1_P$2") (pintype "bidirectional"))
    )
    (net (code "82") (name "X3") (class "Default")
      (node (ref "JP10") (pin "5") (pinfunction "5_5") (pintype "passive"))
      (node (ref "U$3") (pin "P$2") (pinfunction "X1_P$2") (pintype "bidirectional"))
    )
    (net (code "83") (name "X4") (class "Default")
      (node (ref "JP10") (pin "7") (pinfunction "7_7") (pintype "passive"))
      (node (ref "U$4") (pin "P$2") (pinfunction "X1_P$2") (pintype "bidirectional"))
    )
    (net (code "84") (name "X5") (class "Default")
      (node (ref "JP10") (pin "9") (pinfunction "9_9") (pintype "passive"))
      (node (ref "U$5") (pin "P$2") (pinfunction "X1_P$2") (pintype "bidirectional"))
    )
    (net (code "85") (name "X6") (class "Default")
      (node (ref "JP10") (pin "11") (pinfunction "11_11") (pintype "passive"))
      (node (ref "U$6") (pin "P$2") (pinfunction "X1_P$2") (pintype "bidirectional"))
    )
    (net (code "86") (name "XL1") (class "Default")
      (node (ref "JP10") (pin "2") (pinfunction "2_2") (pintype "passive"))
      (node (ref "U$1") (pin "P$1") (pinfunction "LEDC_P$1") (pintype "bidirectional"))
    )
    (net (code "87") (name "XL2") (class "Default")
      (node (ref "JP10") (pin "4") (pinfunction "4_4") (pintype "passive"))
      (node (ref "U$2") (pin "P$1") (pinfunction "LEDC_P$1") (pintype "bidirectional"))
    )
    (net (code "88") (name "XL3") (class "Default")
      (node (ref "JP10") (pin "6") (pinfunction "6_6") (pintype "passive"))
      (node (ref "U$3") (pin "P$1") (pinfunction "LEDC_P$1") (pintype "bidirectional"))
    )
    (net (code "89") (name "XL4") (class "Default")
      (node (ref "JP10") (pin "8") (pinfunction "8_8") (pintype "passive"))
      (node (ref "U$4") (pin "P$1") (pinfunction "LEDC_P$1") (pintype "bidirectional"))
    )
    (net (code "90") (name "XL5") (class "Default")
      (node (ref "JP10") (pin "10") (pinfunction "10_10") (pintype "passive"))
      (node (ref "U$5") (pin "P$1") (pinfunction "LEDC_P$1") (pintype "bidirectional"))
    )
    (net (code "91") (name "XL6") (class "Default")
      (node (ref "JP10") (pin "12") (pinfunction "12_12") (pintype "passive"))
      (node (ref "U$6") (pin "P$1") (pinfunction "LEDC_P$1") (pintype "bidirectional"))
    )
    (net (code "92") (name "unconnected-(JA1-Pad2)") (class "Default")
      (node (ref "JA1") (pin "2") (pinfunction "2_2") (pintype "passive"))
    )
    (net (code "93") (name "unconnected-(JA2-Pad2)") (class "Default")
      (node (ref "JA2") (pin "2") (pinfunction "2_2") (pintype "passive"))
    )
    (net (code "94") (name "unconnected-(JA3-Pad2)") (class "Default")
      (node (ref "JA3") (pin "2") (pinfunction "2_2") (pintype "passive"))
    )
    (net (code "95") (name "unconnected-(JA4-Pad2)") (class "Default")
      (node (ref "JA4") (pin "2") (pinfunction "2_2") (pintype "passive"))
    )
    (net (code "96") (name "unconnected-(JA5-Pad2)") (class "Default")
      (node (ref "JA5") (pin "2") (pinfunction "2_2") (pintype "passive"))
    )
    (net (code "97") (name "unconnected-(JA6-Pad2)") (class "Default")
      (node (ref "JA6") (pin "2") (pinfunction "2_2") (pintype "passive"))
    )
    (net (code "98") (name "unconnected-(JA7-Pad2)") (class "Default")
      (node (ref "JA7") (pin "2") (pinfunction "2_2") (pintype "passive"))
    )
    (net (code "99") (name "unconnected-(JA8-Pad2)") (class "Default")
      (node (ref "JA8") (pin "2") (pinfunction "2_2") (pintype "passive"))
    )
    (net (code "100") (name "unconnected-(JA9-Pad2)") (class "Default")
      (node (ref "JA9") (pin "2") (pinfunction "2_2") (pintype "passive"))
    )
    (net (code "101") (name "unconnected-(JA10-Pad2)") (class "Default")
      (node (ref "JA10") (pin "2") (pinfunction "2_2") (pintype "passive"))
    )
    (net (code "102") (name "unconnected-(JA11-Pad2)") (class "Default")
      (node (ref "JA11") (pin "2") (pinfunction "2_2") (pintype "passive"))
    )
    (net (code "103") (name "unconnected-(JA12-Pad2)") (class "Default")
      (node (ref "JA12") (pin "2") (pinfunction "2_2") (pintype "passive"))
    )
    (net (code "104") (name "unconnected-(JA13-Pad2)") (class "Default")
      (node (ref "JA13") (pin "2") (pinfunction "2_2") (pintype "passive"))
    )
    (net (code "105") (name "unconnected-(JA14-Pad2)") (class "Default")
      (node (ref "JA14") (pin "2") (pinfunction "2_2") (pintype "passive"))
    )
    (net (code "106") (name "unconnected-(JA15-Pad2)") (class "Default")
      (node (ref "JA15") (pin "2") (pinfunction "2_2") (pintype "passive"))
    )
    (net (code "107") (name "unconnected-(JA16-Pad2)") (class "Default")
      (node (ref "JA16") (pin "2") (pinfunction "2_2") (pintype "passive"))
    )
    (net (code "108") (name "unconnected-(JD1-Pad2)") (class "Default")
      (node (ref "JD1") (pin "2") (pinfunction "2_2") (pintype "passive"))
    )
    (net (code "109") (name "unconnected-(JD2-Pad2)") (class "Default")
      (node (ref "JD2") (pin "2") (pinfunction "2_2") (pintype "passive"))
    )
    (net (code "110") (name "unconnected-(JD3-Pad2)") (class "Default")
      (node (ref "JD3") (pin "2") (pinfunction "2_2") (pintype "passive"))
    )
    (net (code "111") (name "unconnected-(JD4-Pad2)") (class "Default")
      (node (ref "JD4") (pin "2") (pinfunction "2_2") (pintype "passive"))
    )
    (net (code "112") (name "unconnected-(JD5-Pad2)") (class "Default")
      (node (ref "JD5") (pin "2") (pinfunction "2_2") (pintype "passive"))
    )
    (net (code "113") (name "unconnected-(JD6-Pad2)") (class "Default")
      (node (ref "JD6") (pin "2") (pinfunction "2_2") (pintype "passive"))
    )
    (net (code "114") (name "unconnected-(JD7-Pad2)") (class "Default")
      (node (ref "JD7") (pin "2") (pinfunction "2_2") (pintype "passive"))
    )
    (net (code "115") (name "unconnected-(JD8-Pad2)") (class "Default")
      (node (ref "JD8") (pin "2") (pinfunction "2_2") (pintype "passive"))
    )
    (net (code "116") (name "unconnected-(JI1-Pad2)") (class "Default")
      (node (ref "JI1") (pin "2") (pinfunction "2_2") (pintype "passive"))
    )
    (net (code "117") (name "unconnected-(JI2-Pad2)") (class "Default")
      (node (ref "JI2") (pin "2") (pinfunction "2_2") (pintype "passive"))
    )
    (net (code "118") (name "unconnected-(JI3-Pad2)") (class "Default")
      (node (ref "JI3") (pin "2") (pinfunction "2_2") (pintype "passive"))
    )
    (net (code "119") (name "unconnected-(JI4-Pad2)") (class "Default")
      (node (ref "JI4") (pin "2") (pinfunction "2_2") (pintype "passive"))
    )
    (net (code "120") (name "unconnected-(JI5-Pad2)") (class "Default")
      (node (ref "JI5") (pin "2") (pinfunction "2_2") (pintype "passive"))
    )
    (net (code "121") (name "unconnected-(JI6-Pad2)") (class "Default")
      (node (ref "JI6") (pin "2") (pinfunction "2_2") (pintype "passive"))
    )
    (net (code "122") (name "unconnected-(JI7-Pad2)") (class "Default")
      (node (ref "JI7") (pin "2") (pinfunction "2_2") (pintype "passive"))
    )
    (net (code "123") (name "unconnected-(JI8-Pad2)") (class "Default")
      (node (ref "JI8") (pin "2") (pinfunction "2_2") (pintype "passive"))
    )
    (net (code "124") (name "unconnected-(X1-S1-PadM1)") (class "Default")
      (node (ref "X1") (pin "M1") (pinfunction "S1_M1") (pintype "passive"))
    )
    (net (code "125") (name "unconnected-(X1-S2-PadM2)") (class "Default")
      (node (ref "X1") (pin "M2") (pinfunction "S2_M2") (pintype "passive"))
    )
    (net (code "126") (name "unconnected-(X2-S1-PadM1)") (class "Default")
      (node (ref "X2") (pin "M1") (pinfunction "S1_M1") (pintype "passive"))
    )
    (net (code "127") (name "unconnected-(X2-S2-PadM2)") (class "Default")
      (node (ref "X2") (pin "M2") (pinfunction "S2_M2") (pintype "passive"))
    )
  )
)
